# PV_Shutdown.net
KiCad netlist of a schematic drawn in Altium Designer
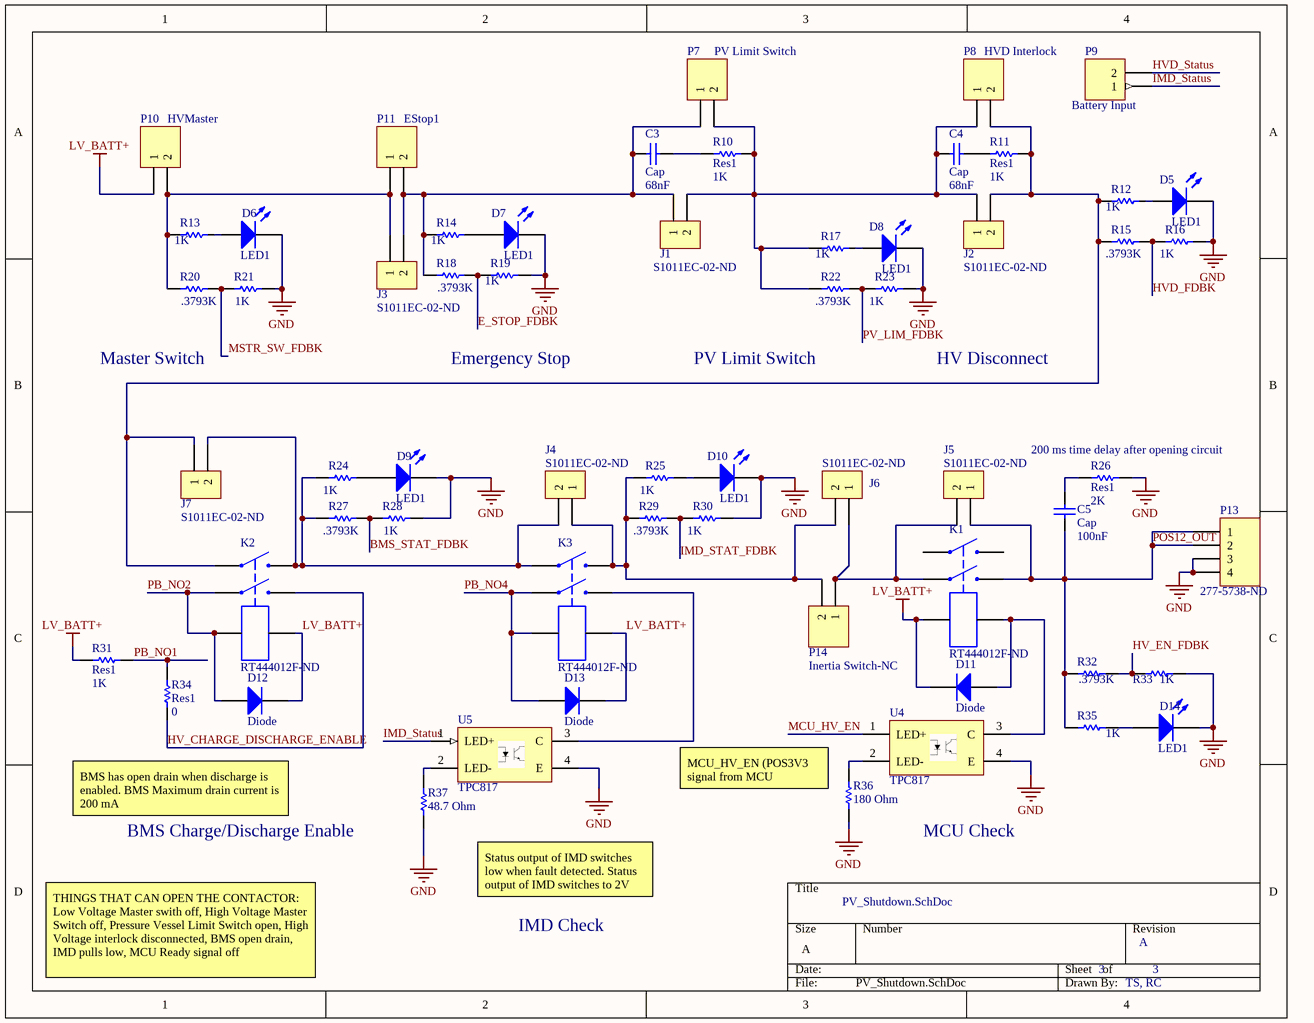
[diagram p0: PV_Shutdown.SchDoc]

(export (version "E")
  (design (tool "Eeschema 10.0.6"))
  (components
    (comp (ref "C3")
      (value "Cap")
      (footprint "1206")
      (description "Capacitor")
      (fields (field (name "ALTIUM_VALUE") "68nF") (field (name "PUBLISHER") "Altium Limited"))
      (libsource (lib "Miscellaneous Devices") (part "Cap"))
    )
    (comp (ref "C4")
      (value "Cap")
      (footprint "1206")
      (description "Capacitor")
      (fields (field (name "ALTIUM_VALUE") "68nF") (field (name "PUBLISHER") "Altium Limited"))
      (libsource (lib "Miscellaneous Devices") (part "Cap"))
    )
    (comp (ref "C5")
      (value "Cap")
      (footprint "1206")
      (description "Capacitor")
      (fields (field (name "ALTIUM_VALUE") "100nF") (field (name "PUBLISHER") "Altium Limited"))
      (libsource (lib "Miscellaneous Devices") (part "Cap"))
    )
    (comp (ref "D5")
      (value "LED1")
      (footprint "1206 LED")
      (description "Typical RED GaAs LED")
      (fields (field (name "PUBLISHER") "Altium Limited"))
      (libsource (lib "Miscellaneous Devices") (part "LED1"))
    )
    (comp (ref "D6")
      (value "LED1")
      (footprint "1206 LED")
      (description "Typical RED GaAs LED")
      (fields (field (name "PUBLISHER") "Altium Limited"))
      (libsource (lib "Miscellaneous Devices") (part "LED1"))
    )
    (comp (ref "D7")
      (value "LED1")
      (footprint "1206 LED")
      (description "Typical RED GaAs LED")
      (fields (field (name "PUBLISHER") "Altium Limited"))
      (libsource (lib "Miscellaneous Devices") (part "LED1"))
    )
    (comp (ref "D8")
      (value "LED1")
      (footprint "1206 LED")
      (description "Typical RED GaAs LED")
      (fields (field (name "PUBLISHER") "Altium Limited"))
      (libsource (lib "Miscellaneous Devices") (part "LED1"))
    )
    (comp (ref "D9")
      (value "LED1")
      (footprint "1206 LED")
      (description "Typical RED GaAs LED")
      (fields (field (name "PUBLISHER") "Altium Limited"))
      (libsource (lib "Miscellaneous Devices") (part "LED1"))
    )
    (comp (ref "D10")
      (value "LED1")
      (footprint "1206 LED")
      (description "Typical RED GaAs LED")
      (fields (field (name "PUBLISHER") "Altium Limited"))
      (libsource (lib "Miscellaneous Devices") (part "LED1"))
    )
    (comp (ref "D11")
      (value "Diode")
      (footprint "1N4007")
      (description "Default Diode")
      (fields (field (name "PUBLISHER") "Altium Limited"))
      (libsource (lib "Miscellaneous Devices") (part "Diode"))
    )
    (comp (ref "D12")
      (value "Diode")
      (footprint "1N4007")
      (description "Default Diode")
      (fields (field (name "PUBLISHER") "Altium Limited"))
      (libsource (lib "Miscellaneous Devices") (part "Diode"))
    )
    (comp (ref "D13")
      (value "Diode")
      (footprint "1N4007")
      (description "Default Diode")
      (fields (field (name "PUBLISHER") "Altium Limited"))
      (libsource (lib "Miscellaneous Devices") (part "Diode"))
    )
    (comp (ref "D14")
      (value "LED1")
      (footprint "1206 LED")
      (description "Typical RED GaAs LED")
      (fields (field (name "PUBLISHER") "Altium Limited"))
      (libsource (lib "Miscellaneous Devices") (part "LED1"))
    )
    (comp (ref "J1")
      (value "S1011EC-02-ND")
      (footprint "2 Pin Jumper")
      (description "CONN HEADER .100\" SNGL STR 2POS")
      (libsource (lib "connector") (part "S1011EC-02-ND"))
    )
    (comp (ref "J2")
      (value "S1011EC-02-ND")
      (footprint "2 Pin Jumper")
      (description "CONN HEADER .100\" SNGL STR 2POS")
      (libsource (lib "connector") (part "S1011EC-02-ND"))
    )
    (comp (ref "J3")
      (value "S1011EC-02-ND")
      (footprint "2 Pin Jumper")
      (description "CONN HEADER .100\" SNGL STR 2POS")
      (libsource (lib "connector") (part "S1011EC-02-ND"))
    )
    (comp (ref "J4")
      (value "S1011EC-02-ND")
      (footprint "2 Pin Jumper")
      (description "CONN HEADER .100\" SNGL STR 2POS")
      (libsource (lib "") (part "S1011EC-02-ND_1"))
    )
    (comp (ref "J5")
      (value "S1011EC-02-ND")
      (footprint "2 Pin Jumper")
      (description "CONN HEADER .100\" SNGL STR 2POS")
      (libsource (lib "") (part "S1011EC-02-ND_1"))
    )
    (comp (ref "J6")
      (value "S1011EC-02-ND")
      (footprint "2 Pin Jumper")
      (description "CONN HEADER .100\" SNGL STR 2POS")
      (libsource (lib "") (part "S1011EC-02-ND_1"))
    )
    (comp (ref "J7")
      (value "S1011EC-02-ND")
      (footprint "2 Pin Jumper")
      (description "CONN HEADER .100\" SNGL STR 2POS")
      (libsource (lib "connector") (part "S1011EC-02-ND"))
    )
    (comp (ref "K1")
      (value "RT444012F-ND")
      (footprint "RT444012F")
      (description "RELAY GEN PURPOSE DPST 8A 12V")
      (libsource (lib "ic") (part "RT444012F-ND"))
    )
    (comp (ref "K2")
      (value "RT444012F-ND")
      (footprint "RT444012F")
      (description "RELAY GEN PURPOSE DPST 8A 12V")
      (libsource (lib "ic") (part "RT444012F-ND"))
    )
    (comp (ref "K3")
      (value "RT444012F-ND")
      (footprint "RT444012F")
      (description "RELAY GEN PURPOSE DPST 8A 12V")
      (libsource (lib "ic") (part "RT444012F-ND"))
    )
    (comp (ref "P7")
      (value "PV Limit Switch")
      (footprint "2POS TERM BLOCK")
      (description "277-5733-ND")
      (fields (field (name "PUBLISHER") "Altium Limited"))
      (libsource (lib "Miscellaneous Connectors") (part "Header 2"))
    )
    (comp (ref "P8")
      (value "HVD Interlock")
      (footprint "2POS TERM BLOCK")
      (description "277-5733-ND")
      (fields (field (name "PUBLISHER") "Altium Limited"))
      (libsource (lib "Miscellaneous Connectors") (part "Header 2"))
    )
    (comp (ref "P9")
      (value "Battery Input")
      (footprint "2POS TERM BLOCK")
      (description "Header, 2-Pin")
      (fields (field (name "PUBLISHER") "Altium Limited"))
      (libsource (lib "") (part "Header 2_2"))
    )
    (comp (ref "P10")
      (value "HVMaster")
      (footprint "2POS TERM BLOCK")
      (description "277-5733-ND")
      (fields (field (name "PUBLISHER") "Altium Limited"))
      (libsource (lib "Miscellaneous Connectors") (part "Header 2"))
    )
    (comp (ref "P11")
      (value "EStop1")
      (footprint "2POS TERM BLOCK")
      (description "277-5733-ND")
      (fields (field (name "PUBLISHER") "Altium Limited"))
      (libsource (lib "Miscellaneous Connectors") (part "Header 2"))
    )
    (comp (ref "P13")
      (value "277-5738-ND")
      (footprint "4POS TERM BLOCK")
      (description "Header, 4-Pin")
      (fields (field (name "PUBLISHER") "Altium Limited"))
      (libsource (lib "Miscellaneous Connectors") (part "Header 4"))
    )
    (comp (ref "P14")
      (value "Inertia Switch-NC")
      (footprint "2POS TERM BLOCK")
      (description "277-5733-ND")
      (fields (field (name "PUBLISHER") "Altium Limited"))
      (libsource (lib "") (part "Header 2_1"))
    )
    (comp (ref "R10")
      (value "Res1")
      (footprint "1206")
      (description "Resistor")
      (fields (field (name "ALTIUM_VALUE") "1K") (field (name "PUBLISHER") "Altium Limited"))
      (libsource (lib "Miscellaneous Devices") (part "Res1"))
    )
    (comp (ref "R11")
      (value "Res1")
      (footprint "1206")
      (description "Resistor")
      (fields (field (name "ALTIUM_VALUE") "1K") (field (name "PUBLISHER") "Altium Limited"))
      (libsource (lib "Miscellaneous Devices") (part "Res1"))
    )
    (comp (ref "R12")
      (value "1K")
      (footprint "1206")
      (description "Resistor")
      (fields (field (name "Comment") "Res1") (field (name "PUBLISHER") "Altium Limited"))
      (libsource (lib "Miscellaneous Devices") (part "Res1"))
    )
    (comp (ref "R13")
      (value "1K")
      (footprint "1206")
      (description "Resistor")
      (fields (field (name "Comment") "Res1") (field (name "PUBLISHER") "Altium Limited"))
      (libsource (lib "Miscellaneous Devices") (part "Res1"))
    )
    (comp (ref "R14")
      (value "1K")
      (footprint "1206")
      (description "Resistor")
      (fields (field (name "Comment") "Res1") (field (name "PUBLISHER") "Altium Limited"))
      (libsource (lib "Miscellaneous Devices") (part "Res1"))
    )
    (comp (ref "R15")
      (value ".3793K")
      (footprint "1206")
      (description "Resistor")
      (fields (field (name "Comment") "Res1") (field (name "PUBLISHER") "Altium Limited"))
      (libsource (lib "Miscellaneous Devices") (part "Res1"))
    )
    (comp (ref "R16")
      (value "1K")
      (footprint "1206")
      (description "Resistor")
      (fields (field (name "Comment") "Res1") (field (name "PUBLISHER") "Altium Limited"))
      (libsource (lib "Miscellaneous Devices") (part "Res1"))
    )
    (comp (ref "R17")
      (value "1K")
      (footprint "1206")
      (description "Resistor")
      (fields (field (name "Comment") "Res1") (field (name "PUBLISHER") "Altium Limited"))
      (libsource (lib "Miscellaneous Devices") (part "Res1"))
    )
    (comp (ref "R18")
      (value ".3793K")
      (footprint "1206")
      (description "Resistor")
      (fields (field (name "Comment") "Res1") (field (name "PUBLISHER") "Altium Limited"))
      (libsource (lib "Miscellaneous Devices") (part "Res1"))
    )
    (comp (ref "R19")
      (value "1K")
      (footprint "1206")
      (description "Resistor")
      (fields (field (name "Comment") "Res1") (field (name "PUBLISHER") "Altium Limited"))
      (libsource (lib "Miscellaneous Devices") (part "Res1"))
    )
    (comp (ref "R20")
      (value ".3793K")
      (footprint "1206")
      (description "Resistor")
      (fields (field (name "Comment") "Res1") (field (name "PUBLISHER") "Altium Limited"))
      (libsource (lib "Miscellaneous Devices") (part "Res1"))
    )
    (comp (ref "R21")
      (value "1K")
      (footprint "1206")
      (description "Resistor")
      (fields (field (name "Comment") "Res1") (field (name "PUBLISHER") "Altium Limited"))
      (libsource (lib "Miscellaneous Devices") (part "Res1"))
    )
    (comp (ref "R22")
      (value ".3793K")
      (footprint "1206")
      (description "Resistor")
      (fields (field (name "Comment") "Res1") (field (name "PUBLISHER") "Altium Limited"))
      (libsource (lib "Miscellaneous Devices") (part "Res1"))
    )
    (comp (ref "R23")
      (value "1K")
      (footprint "1206")
      (description "Resistor")
      (fields (field (name "Comment") "Res1") (field (name "PUBLISHER") "Altium Limited"))
      (libsource (lib "Miscellaneous Devices") (part "Res1"))
    )
    (comp (ref "R24")
      (value "1K")
      (footprint "1206")
      (description "Resistor")
      (fields (field (name "Comment") "Res1") (field (name "PUBLISHER") "Altium Limited"))
      (libsource (lib "Miscellaneous Devices") (part "Res1"))
    )
    (comp (ref "R25")
      (value "1K")
      (footprint "1206")
      (description "Resistor")
      (fields (field (name "Comment") "Res1") (field (name "PUBLISHER") "Altium Limited"))
      (libsource (lib "Miscellaneous Devices") (part "Res1"))
    )
    (comp (ref "R26")
      (value "Res1")
      (footprint "1206")
      (description "Resistor")
      (fields (field (name "ALTIUM_VALUE") "2K") (field (name "PUBLISHER") "Altium Limited"))
      (libsource (lib "Miscellaneous Devices") (part "Res1"))
    )
    (comp (ref "R27")
      (value ".3793K")
      (footprint "1206")
      (description "Resistor")
      (fields (field (name "Comment") "Res1") (field (name "PUBLISHER") "Altium Limited"))
      (libsource (lib "Miscellaneous Devices") (part "Res1"))
    )
    (comp (ref "R28")
      (value "1K")
      (footprint "1206")
      (description "Resistor")
      (fields (field (name "Comment") "Res1") (field (name "PUBLISHER") "Altium Limited"))
      (libsource (lib "Miscellaneous Devices") (part "Res1"))
    )
    (comp (ref "R29")
      (value ".3793K")
      (footprint "1206")
      (description "Resistor")
      (fields (field (name "Comment") "Res1") (field (name "PUBLISHER") "Altium Limited"))
      (libsource (lib "Miscellaneous Devices") (part "Res1"))
    )
    (comp (ref "R30")
      (value "1K")
      (footprint "1206")
      (description "Resistor")
      (fields (field (name "Comment") "Res1") (field (name "PUBLISHER") "Altium Limited"))
      (libsource (lib "Miscellaneous Devices") (part "Res1"))
    )
    (comp (ref "R31")
      (value "Res1")
      (footprint "1206")
      (description "Resistor")
      (fields (field (name "ALTIUM_VALUE") "1K") (field (name "PUBLISHER") "Altium Limited"))
      (libsource (lib "Miscellaneous Devices") (part "Res1"))
    )
    (comp (ref "R32")
      (value ".3793K")
      (footprint "1206")
      (description "Resistor")
      (fields (field (name "Comment") "Res1") (field (name "PUBLISHER") "Altium Limited"))
      (libsource (lib "Miscellaneous Devices") (part "Res1"))
    )
    (comp (ref "R33")
      (value "1K")
      (footprint "1206")
      (description "Resistor")
      (fields (field (name "Comment") "Res1") (field (name "PUBLISHER") "Altium Limited"))
      (libsource (lib "Miscellaneous Devices") (part "Res1"))
    )
    (comp (ref "R34")
      (value "Res1")
      (footprint "1206")
      (description "Resistor")
      (fields (field (name "ALTIUM_VALUE") "0") (field (name "PUBLISHER") "Altium Limited"))
      (libsource (lib "Miscellaneous Devices") (part "Res1"))
    )
    (comp (ref "R35")
      (value "1K")
      (footprint "1206")
      (description "Resistor")
      (fields (field (name "Comment") "Res1") (field (name "PUBLISHER") "Altium Limited"))
      (libsource (lib "Miscellaneous Devices") (part "Res1"))
    )
    (comp (ref "R36")
      (value "180 Ohm")
      (footprint "1206")
      (description "Resistor")
      (fields (field (name "Comment") "Res1") (field (name "PUBLISHER") "Altium Limited"))
      (libsource (lib "Miscellaneous Devices") (part "Res1"))
    )
    (comp (ref "R37")
      (value "48.7 Ohm")
      (footprint "1206")
      (description "Resistor")
      (fields (field (name "Comment") "Res1") (field (name "PUBLISHER") "Altium Limited"))
      (libsource (lib "Miscellaneous Devices") (part "Res1"))
    )
    (comp (ref "U4")
      (value "TPC817")
      (footprint "4-SOP")
      (description "Opto-Coupler")
      (libsource (lib "ic") (part "TPC817"))
    )
    (comp (ref "U5")
      (value "TPC817")
      (footprint "4-SOP")
      (description "Opto-Coupler")
      (libsource (lib "ic") (part "TPC817"))
    )
  )
  (nets
    (net (code "1") (name "/BMS_STAT_FDBK") (class "Default")
      (node (ref "R27") (pin "1") (pinfunction "1_1") (pintype "passive"))
      (node (ref "R28") (pin "2") (pinfunction "2_2") (pintype "passive"))
    )
    (net (code "2") (name "/E_STOP_FDBK") (class "Default")
      (node (ref "R18") (pin "1") (pinfunction "1_1") (pintype "passive"))
      (node (ref "R19") (pin "2") (pinfunction "2_2") (pintype "passive"))
    )
    (net (code "3") (name "/HVD_FDBK") (class "Default")
      (node (ref "R15") (pin "1") (pinfunction "1_1") (pintype "passive"))
      (node (ref "R16") (pin "2") (pinfunction "2_2") (pintype "passive"))
    )
    (net (code "4") (name "/HVD_Status") (class "Default")
      (node (ref "P9") (pin "2") (pinfunction "2_2") (pintype "passive"))
    )
    (net (code "5") (name "/HV_CHARGE_DISCHARGE_ENABLE") (class "Default")
      (node (ref "K2") (pin "4") (pinfunction "4_4") (pintype "passive"))
      (node (ref "R34") (pin "1") (pinfunction "1_1") (pintype "passive"))
    )
    (net (code "6") (name "/HV_EN_FDBK") (class "Default")
      (node (ref "R32") (pin "1") (pinfunction "1_1") (pintype "passive"))
      (node (ref "R33") (pin "2") (pinfunction "2_2") (pintype "passive"))
    )
    (net (code "7") (name "/IMD_STAT_FDBK") (class "Default")
      (node (ref "R29") (pin "1") (pinfunction "1_1") (pintype "passive"))
      (node (ref "R30") (pin "2") (pinfunction "2_2") (pintype "passive"))
    )
    (net (code "8") (name "/IMD_Status") (class "Default")
      (node (ref "P9") (pin "1") (pinfunction "1_1") (pintype "output"))
      (node (ref "U5") (pin "1") (pinfunction "LED+_1") (pintype "input"))
    )
    (net (code "9") (name "/MCU_HV_EN") (class "Default")
      (node (ref "U4") (pin "1") (pinfunction "LED+_1") (pintype "input"))
    )
    (net (code "10") (name "/MSTR_SW_FDBK") (class "Default")
      (node (ref "R20") (pin "1") (pinfunction "1_1") (pintype "passive"))
      (node (ref "R21") (pin "2") (pinfunction "2_2") (pintype "passive"))
    )
    (net (code "11") (name "/PB_NO1") (class "Default")
      (node (ref "R31") (pin "2") (pinfunction "2_2") (pintype "passive"))
      (node (ref "R34") (pin "2") (pinfunction "2_2") (pintype "passive"))
    )
    (net (code "12") (name "/PB_NO2") (class "Default")
      (node (ref "D12") (pin "1") (pinfunction "A_1") (pintype "passive"))
      (node (ref "K2") (pin "1") (pinfunction "1_1") (pintype "passive"))
      (node (ref "K2") (pin "3") (pinfunction "3_3") (pintype "passive"))
    )
    (net (code "13") (name "/PB_NO4") (class "Default")
      (node (ref "D13") (pin "1") (pinfunction "A_1") (pintype "passive"))
      (node (ref "K3") (pin "1") (pinfunction "1_1") (pintype "passive"))
      (node (ref "K3") (pin "3") (pinfunction "3_3") (pintype "passive"))
    )
    (net (code "14") (name "/POS12_OUT") (class "Default")
      (node (ref "C5") (pin "1") (pinfunction "1_1") (pintype "passive"))
      (node (ref "J5") (pin "1") (pinfunction "1_1") (pintype "passive"))
      (node (ref "K1") (pin "4") (pinfunction "4_4") (pintype "passive"))
      (node (ref "P13") (pin "1") (pinfunction "1_1") (pintype "passive"))
      (node (ref "P13") (pin "2") (pinfunction "2_2") (pintype "passive"))
      (node (ref "R32") (pin "2") (pinfunction "2_2") (pintype "passive"))
      (node (ref "R35") (pin "2") (pinfunction "2_2") (pintype "passive"))
    )
    (net (code "15") (name "/PV_LIM_FDBK") (class "Default")
      (node (ref "R22") (pin "1") (pinfunction "1_1") (pintype "passive"))
      (node (ref "R23") (pin "2") (pinfunction "2_2") (pintype "passive"))
    )
    (net (code "16") (name "GND") (class "Default")
      (node (ref "D10") (pin "2") (pinfunction "K_2") (pintype "passive"))
      (node (ref "D14") (pin "2") (pinfunction "K_2") (pintype "passive"))
      (node (ref "D5") (pin "2") (pinfunction "K_2") (pintype "passive"))
      (node (ref "D6") (pin "2") (pinfunction "K_2") (pintype "passive"))
      (node (ref "D7") (pin "2") (pinfunction "K_2") (pintype "passive"))
      (node (ref "D8") (pin "2") (pinfunction "K_2") (pintype "passive"))
      (node (ref "D9") (pin "2") (pinfunction "K_2") (pintype "passive"))
      (node (ref "P13") (pin "3") (pinfunction "3_3") (pintype "passive"))
      (node (ref "P13") (pin "4") (pinfunction "4_4") (pintype "passive"))
      (node (ref "R16") (pin "1") (pinfunction "1_1") (pintype "passive"))
      (node (ref "R19") (pin "1") (pinfunction "1_1") (pintype "passive"))
      (node (ref "R21") (pin "1") (pinfunction "1_1") (pintype "passive"))
      (node (ref "R23") (pin "1") (pinfunction "1_1") (pintype "passive"))
      (node (ref "R26") (pin "2") (pinfunction "2_2") (pintype "passive"))
      (node (ref "R28") (pin "1") (pinfunction "1_1") (pintype "passive"))
      (node (ref "R30") (pin "1") (pinfunction "1_1") (pintype "passive"))
      (node (ref "R33") (pin "1") (pinfunction "1_1") (pintype "passive"))
      (node (ref "R36") (pin "2") (pinfunction "2_2") (pintype "passive"))
      (node (ref "R37") (pin "2") (pinfunction "2_2") (pintype "passive"))
      (node (ref "U4") (pin "4") (pinfunction "E_4") (pintype "passive"))
      (node (ref "U5") (pin "4") (pinfunction "E_4") (pintype "passive"))
    )
    (net (code "17") (name "LV_BATT+") (class "Default")
      (node (ref "D11") (pin "2") (pinfunction "K_2") (pintype "passive"))
      (node (ref "D12") (pin "2") (pinfunction "K_2") (pintype "passive"))
      (node (ref "D13") (pin "2") (pinfunction "K_2") (pintype "passive"))
      (node (ref "K1") (pin "1") (pinfunction "1_1") (pintype "passive"))
      (node (ref "K2") (pin "2") (pinfunction "2_2") (pintype "passive"))
      (node (ref "K3") (pin "2") (pinfunction "2_2") (pintype "passive"))
      (node (ref "P10") (pin "1") (pinfunction "1_1") (pintype "passive"))
      (node (ref "R31") (pin "1") (pinfunction "1_1") (pintype "passive"))
    )
    (net (code "18") (name "Net-(C3-Pad1)") (class "Default")
      (node (ref "C3") (pin "1") (pinfunction "1_1") (pintype "passive"))
      (node (ref "J1") (pin "1") (pinfunction "1_1") (pintype "passive"))
      (node (ref "J3") (pin "2") (pinfunction "2_2") (pintype "passive"))
      (node (ref "P11") (pin "2") (pinfunction "2_2") (pintype "passive"))
      (node (ref "P7") (pin "1") (pinfunction "1_1") (pintype "passive"))
      (node (ref "R14") (pin "1") (pinfunction "1_1") (pintype "passive"))
      (node (ref "R18") (pin "2") (pinfunction "2_2") (pintype "passive"))
    )
    (net (code "19") (name "Net-(C3-Pad2)") (class "Default")
      (node (ref "C3") (pin "2") (pinfunction "2_2") (pintype "passive"))
      (node (ref "R10") (pin "1") (pinfunction "1_1") (pintype "passive"))
    )
    (net (code "20") (name "Net-(C4-Pad1)") (class "Default")
      (node (ref "C4") (pin "1") (pinfunction "1_1") (pintype "passive"))
      (node (ref "J1") (pin "2") (pinfunction "2_2") (pintype "passive"))
      (node (ref "J2") (pin "1") (pinfunction "1_1") (pintype "passive"))
      (node (ref "P7") (pin "2") (pinfunction "2_2") (pintype "passive"))
      (node (ref "P8") (pin "1") (pinfunction "1_1") (pintype "passive"))
      (node (ref "R10") (pin "2") (pinfunction "2_2") (pintype "passive"))
      (node (ref "R17") (pin "1") (pinfunction "1_1") (pintype "passive"))
      (node (ref "R22") (pin "2") (pinfunction "2_2") (pintype "passive"))
    )
    (net (code "21") (name "Net-(C4-Pad2)") (class "Default")
      (node (ref "C4") (pin "2") (pinfunction "2_2") (pintype "passive"))
      (node (ref "R11") (pin "1") (pinfunction "1_1") (pintype "passive"))
    )
    (net (code "22") (name "Net-(C5-Pad2)") (class "Default")
      (node (ref "C5") (pin "2") (pinfunction "2_2") (pintype "passive"))
      (node (ref "R26") (pin "1") (pinfunction "1_1") (pintype "passive"))
    )
    (net (code "23") (name "Net-(D5-A)") (class "Default")
      (node (ref "D5") (pin "1") (pinfunction "A_1") (pintype "passive"))
      (node (ref "R12") (pin "2") (pinfunction "2_2") (pintype "passive"))
    )
    (net (code "24") (name "Net-(D6-A)") (class "Default")
      (node (ref "D6") (pin "1") (pinfunction "A_1") (pintype "passive"))
      (node (ref "R13") (pin "2") (pinfunction "2_2") (pintype "passive"))
    )
    (net (code "25") (name "Net-(D7-A)") (class "Default")
      (node (ref "D7") (pin "1") (pinfunction "A_1") (pintype "passive"))
      (node (ref "R14") (pin "2") (pinfunction "2_2") (pintype "passive"))
    )
    (net (code "26") (name "Net-(D8-A)") (class "Default")
      (node (ref "D8") (pin "1") (pinfunction "A_1") (pintype "passive"))
      (node (ref "R17") (pin "2") (pinfunction "2_2") (pintype "passive"))
    )
    (net (code "27") (name "Net-(D9-A)") (class "Default")
      (node (ref "D9") (pin "1") (pinfunction "A_1") (pintype "passive"))
      (node (ref "R24") (pin "2") (pinfunction "2_2") (pintype "passive"))
    )
    (net (code "28") (name "Net-(D10-A)") (class "Default")
      (node (ref "D10") (pin "1") (pinfunction "A_1") (pintype "passive"))
      (node (ref "R25") (pin "2") (pinfunction "2_2") (pintype "passive"))
    )
    (net (code "29") (name "Net-(D11-A)") (class "Default")
      (node (ref "D11") (pin "1") (pinfunction "A_1") (pintype "passive"))
      (node (ref "K1") (pin "2") (pinfunction "2_2") (pintype "passive"))
      (node (ref "U4") (pin "3") (pinfunction "C_3") (pintype "open_collector"))
    )
    (net (code "30") (name "Net-(D14-A)") (class "Default")
      (node (ref "D14") (pin "1") (pinfunction "A_1") (pintype "passive"))
      (node (ref "R35") (pin "1") (pinfunction "1_1") (pintype "passive"))
    )
    (net (code "31") (name "Net-(J2-Pad2)") (class "Default")
      (node (ref "J2") (pin "2") (pinfunction "2_2") (pintype "passive"))
      (node (ref "J7") (pin "1") (pinfunction "1_1") (pintype "passive"))
      (node (ref "K2") (pin "5") (pinfunction "5_5") (pintype "passive"))
      (node (ref "P8") (pin "2") (pinfunction "2_2") (pintype "passive"))
      (node (ref "R11") (pin "2") (pinfunction "2_2") (pintype "passive"))
      (node (ref "R12") (pin "1") (pinfunction "1_1") (pintype "passive"))
      (node (ref "R15") (pin "2") (pinfunction "2_2") (pintype "passive"))
    )
    (net (code "32") (name "Net-(J3-Pad1)") (class "Default")
      (node (ref "J3") (pin "1") (pinfunction "1_1") (pintype "passive"))
      (node (ref "P10") (pin "2") (pinfunction "2_2") (pintype "passive"))
      (node (ref "P11") (pin "1") (pinfunction "1_1") (pintype "passive"))
      (node (ref "R13") (pin "1") (pinfunction "1_1") (pintype "passive"))
      (node (ref "R20") (pin "2") (pinfunction "2_2") (pintype "passive"))
    )
    (net (code "33") (name "Net-(J4-Pad1)") (class "Default")
      (node (ref "J4") (pin "1") (pinfunction "1_1") (pintype "passive"))
      (node (ref "J6") (pin "2") (pinfunction "2_2") (pintype "passive"))
      (node (ref "K3") (pin "6") (pinfunction "6_6") (pintype "passive"))
      (node (ref "P14") (pin "2") (pinfunction "2_2") (pintype "passive"))
      (node (ref "R25") (pin "1") (pinfunction "1_1") (pintype "passive"))
      (node (ref "R29") (pin "2") (pinfunction "2_2") (pintype "passive"))
    )
    (net (code "34") (name "Net-(J4-Pad2)") (class "Default")
      (node (ref "J4") (pin "2") (pinfunction "2_2") (pintype "passive"))
      (node (ref "J7") (pin "2") (pinfunction "2_2") (pintype "passive"))
      (node (ref "K2") (pin "6") (pinfunction "6_6") (pintype "passive"))
      (node (ref "K3") (pin "5") (pinfunction "5_5") (pintype "passive"))
      (node (ref "R24") (pin "1") (pinfunction "1_1") (pintype "passive"))
      (node (ref "R27") (pin "2") (pinfunction "2_2") (pintype "passive"))
    )
    (net (code "35") (name "Net-(J5-Pad2)") (class "Default")
      (node (ref "J5") (pin "2") (pinfunction "2_2") (pintype "passive"))
      (node (ref "J6") (pin "1") (pinfunction "1_1") (pintype "passive"))
      (node (ref "K1") (pin "3") (pinfunction "3_3") (pintype "passive"))
      (node (ref "P14") (pin "1") (pinfunction "1_1") (pintype "passive"))
    )
    (net (code "36") (name "Net-(U4-LED-)") (class "Default")
      (node (ref "R36") (pin "1") (pinfunction "1_1") (pintype "passive"))
      (node (ref "U4") (pin "2") (pinfunction "LED-_2") (pintype "open_emitter"))
    )
    (net (code "37") (name "Net-(U5-C)") (class "Default")
      (node (ref "K3") (pin "4") (pinfunction "4_4") (pintype "passive"))
      (node (ref "U5") (pin "3") (pinfunction "C_3") (pintype "open_collector"))
    )
    (net (code "38") (name "Net-(U5-LED-)") (class "Default")
      (node (ref "R37") (pin "1") (pinfunction "1_1") (pintype "passive"))
      (node (ref "U5") (pin "2") (pinfunction "LED-_2") (pintype "open_emitter"))
    )
    (net (code "39") (name "unconnected-(K1-Pad5)") (class "Default")
      (node (ref "K1") (pin "5") (pinfunction "5_5") (pintype "passive"))
    )
    (net (code "40") (name "unconnected-(K1-Pad6)") (class "Default")
      (node (ref "K1") (pin "6") (pinfunction "6_6") (pintype "passive"))
    )
  )
)
